# c12880ma-spectrometer-3_3v-breakout-mk-1.net
KiCad netlist of a schematic drawn in EAGLE
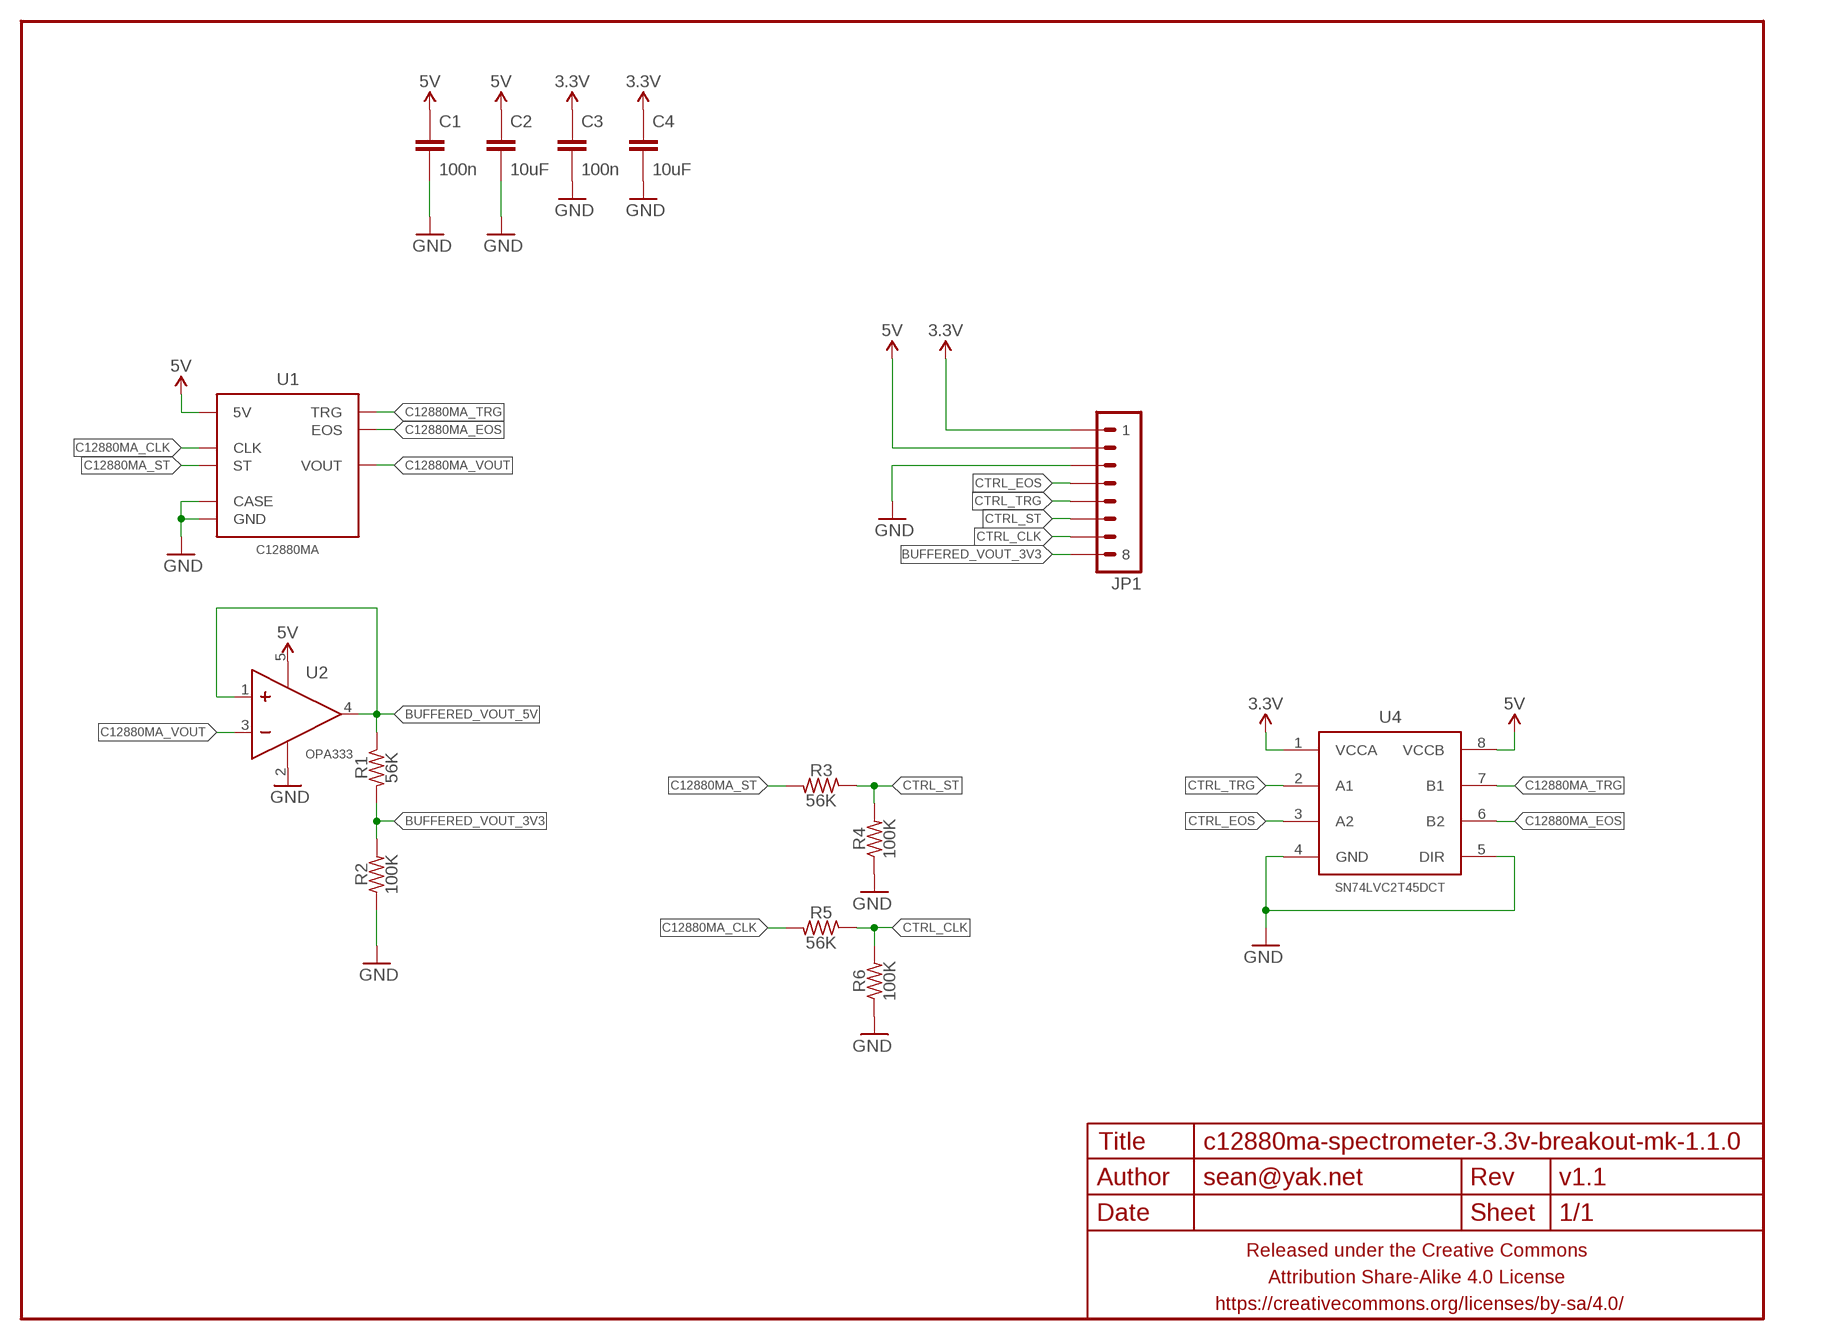
[diagram p0: schematic, sheet 1]

(export (version "E")
  (design (tool "Eeschema 10.0.6"))
  (components
    (comp (ref "C1")
      (value "100n")
      (footprint "eagle-import:C0402")
      (libsource (lib "eagle-import") (part "CAPACITOR-CERAMICC0402"))
    )
    (comp (ref "C2")
      (value "10uF")
      (footprint "eagle-import:C0603-TIGHTER")
      (libsource (lib "eagle-import") (part "CAPACITOR-CERAMICC0603-TIGHTER"))
    )
    (comp (ref "C3")
      (value "100n")
      (footprint "eagle-import:C0402")
      (libsource (lib "eagle-import") (part "CAPACITOR-CERAMICC0402"))
    )
    (comp (ref "C4")
      (value "10uF")
      (footprint "eagle-import:C0603-TIGHTER")
      (libsource (lib "eagle-import") (part "CAPACITOR-CERAMICC0603-TIGHTER"))
    )
    (comp (ref "FRAME1")
      (value "FRAME-LETTERNO_PACKAGE")
      (footprint "eagle-import:DUMMY")
      (fields
        (field (name "DESIGNER") "sean@yak.net")
        (field (name "VERSION") "v1.1")
        (field (name "DESIGNER_1") "sean@yak.net")
        (field (name "VERSION_1") "v1.1")
      )
      (libsource (lib "eagle-import") (part "FRAME-LETTERNO_PACKAGE"))
    )
    (comp (ref "JP1")
      (value "M081X08")
      (footprint "eagle-import:1X08")
      (libsource (lib "eagle-import") (part "M081X08"))
    )
    (comp (ref "R1")
      (value "56K")
      (footprint "eagle-import:R0402")
      (libsource (lib "eagle-import") (part "RESISTORR0402"))
    )
    (comp (ref "R2")
      (value "100K")
      (footprint "eagle-import:R0402")
      (libsource (lib "eagle-import") (part "RESISTORR0402"))
    )
    (comp (ref "R3")
      (value "56K")
      (footprint "eagle-import:R0402")
      (libsource (lib "eagle-import") (part "RESISTORR0402"))
    )
    (comp (ref "R4")
      (value "100K")
      (footprint "eagle-import:R0402")
      (libsource (lib "eagle-import") (part "RESISTORR0402"))
    )
    (comp (ref "R5")
      (value "56K")
      (footprint "eagle-import:R0402")
      (libsource (lib "eagle-import") (part "RESISTORR0402"))
    )
    (comp (ref "R6")
      (value "100K")
      (footprint "eagle-import:R0402")
      (libsource (lib "eagle-import") (part "RESISTORR0402"))
    )
    (comp (ref "U1")
      (value "C12880MA")
      (footprint "eagle-import:DIL14")
      (libsource (lib "eagle-import") (part "C12880MA"))
    )
    (comp (ref "U2")
      (value "OPA333")
      (footprint "eagle-import:SC70")
      (libsource (lib "eagle-import") (part "OPAMPOPA333-SC-70"))
    )
    (comp (ref "U4")
      (value "SN74LVC2T45DCT")
      (footprint "eagle-import:SSOP-8")
      (libsource (lib "eagle-import") (part "SN74LVC2T45DCT"))
    )
  )
  (nets
    (net (code "1") (name "3.3V") (class "Default")
      (node (ref "C3") (pin "1") (pinfunction "1_1") (pintype "passive"))
      (node (ref "C4") (pin "1") (pinfunction "1_1") (pintype "passive"))
      (node (ref "JP1") (pin "1") (pinfunction "1_1") (pintype "passive"))
      (node (ref "U4") (pin "1") (pinfunction "VCCA_1") (pintype "bidirectional"))
    )
    (net (code "2") (name "5V") (class "Default")
      (node (ref "C1") (pin "1") (pinfunction "1_1") (pintype "passive"))
      (node (ref "C2") (pin "1") (pinfunction "1_1") (pintype "passive"))
      (node (ref "JP1") (pin "2") (pinfunction "2_2") (pintype "passive"))
      (node (ref "U1") (pin "1") (pinfunction "5V_1") (pintype "bidirectional"))
      (node (ref "U1") (pin "5") (pinfunction "5V_5") (pintype "bidirectional"))
      (node (ref "U2") (pin "5") (pinfunction "V+_5") (pintype "power_in"))
      (node (ref "U4") (pin "8") (pinfunction "VCCB_8") (pintype "bidirectional"))
    )
    (net (code "3") (name "BUFFERED_VOUT_3V3") (class "Default")
      (node (ref "JP1") (pin "8") (pinfunction "8_8") (pintype "passive"))
      (node (ref "R1") (pin "2") (pinfunction "2_2") (pintype "passive"))
      (node (ref "R2") (pin "2") (pinfunction "2_2") (pintype "passive"))
    )
    (net (code "4") (name "BUFFERED_VOUT_5V") (class "Default")
      (node (ref "R1") (pin "1") (pinfunction "1_1") (pintype "passive"))
      (node (ref "U2") (pin "1") (pinfunction "IN+_1") (pintype "input"))
      (node (ref "U2") (pin "4") (pinfunction "OUT_4") (pintype "output"))
    )
    (net (code "5") (name "C12880MA_CLK") (class "Default")
      (node (ref "R5") (pin "2") (pinfunction "2_2") (pintype "passive"))
      (node (ref "U1") (pin "6") (pinfunction "CLK_6") (pintype "input"))
    )
    (net (code "6") (name "C12880MA_EOS") (class "Default")
      (node (ref "U1") (pin "13") (pinfunction "EOS_13") (pintype "output"))
      (node (ref "U4") (pin "6") (pinfunction "B2_6") (pintype "bidirectional"))
    )
    (net (code "7") (name "C12880MA_ST") (class "Default")
      (node (ref "R3") (pin "2") (pinfunction "2_2") (pintype "passive"))
      (node (ref "U1") (pin "8") (pinfunction "ST_8") (pintype "input"))
    )
    (net (code "8") (name "C12880MA_TRG") (class "Default")
      (node (ref "U1") (pin "9") (pinfunction "TRG_9") (pintype "output"))
      (node (ref "U4") (pin "7") (pinfunction "B1_7") (pintype "bidirectional"))
    )
    (net (code "9") (name "C12880MA_VOUT") (class "Default")
      (node (ref "U1") (pin "14") (pinfunction "VOUT_14") (pintype "output"))
      (node (ref "U2") (pin "3") (pinfunction "IN-_3") (pintype "input"))
    )
    (net (code "10") (name "CTRL_CLK") (class "Default")
      (node (ref "JP1") (pin "7") (pinfunction "7_7") (pintype "passive"))
      (node (ref "R5") (pin "1") (pinfunction "1_1") (pintype "passive"))
      (node (ref "R6") (pin "2") (pinfunction "2_2") (pintype "passive"))
    )
    (net (code "11") (name "CTRL_EOS") (class "Default")
      (node (ref "JP1") (pin "4") (pinfunction "4_4") (pintype "passive"))
      (node (ref "U4") (pin "3") (pinfunction "A2_3") (pintype "bidirectional"))
    )
    (net (code "12") (name "CTRL_ST") (class "Default")
      (node (ref "JP1") (pin "6") (pinfunction "6_6") (pintype "passive"))
      (node (ref "R3") (pin "1") (pinfunction "1_1") (pintype "passive"))
      (node (ref "R4") (pin "2") (pinfunction "2_2") (pintype "passive"))
    )
    (net (code "13") (name "CTRL_TRG") (class "Default")
      (node (ref "JP1") (pin "5") (pinfunction "5_5") (pintype "passive"))
      (node (ref "U4") (pin "2") (pinfunction "A1_2") (pintype "bidirectional"))
    )
    (net (code "14") (name "GND") (class "Default")
      (node (ref "C1") (pin "2") (pinfunction "2_2") (pintype "passive"))
      (node (ref "C2") (pin "2") (pinfunction "2_2") (pintype "passive"))
      (node (ref "C3") (pin "2") (pinfunction "2_2") (pintype "passive"))
      (node (ref "C4") (pin "2") (pinfunction "2_2") (pintype "passive"))
      (node (ref "JP1") (pin "3") (pinfunction "3_3") (pintype "passive"))
      (node (ref "R2") (pin "1") (pinfunction "1_1") (pintype "passive"))
      (node (ref "R4") (pin "1") (pinfunction "1_1") (pintype "passive"))
      (node (ref "R6") (pin "1") (pinfunction "1_1") (pintype "passive"))
      (node (ref "U1") (pin "2") (pinfunction "GND_2") (pintype "bidirectional"))
      (node (ref "U1") (pin "7") (pinfunction "CASE_7") (pintype "bidirectional"))
      (node (ref "U2") (pin "2") (pinfunction "V-_2") (pintype "power_in"))
      (node (ref "U4") (pin "4") (pinfunction "GND_4") (pintype "bidirectional"))
      (node (ref "U4") (pin "5") (pinfunction "DIR_5") (pintype "bidirectional"))
    )
  )
)
